# MACH_NGUYEN_LY.net
KiCad netlist of a schematic drawn in Altium Designer
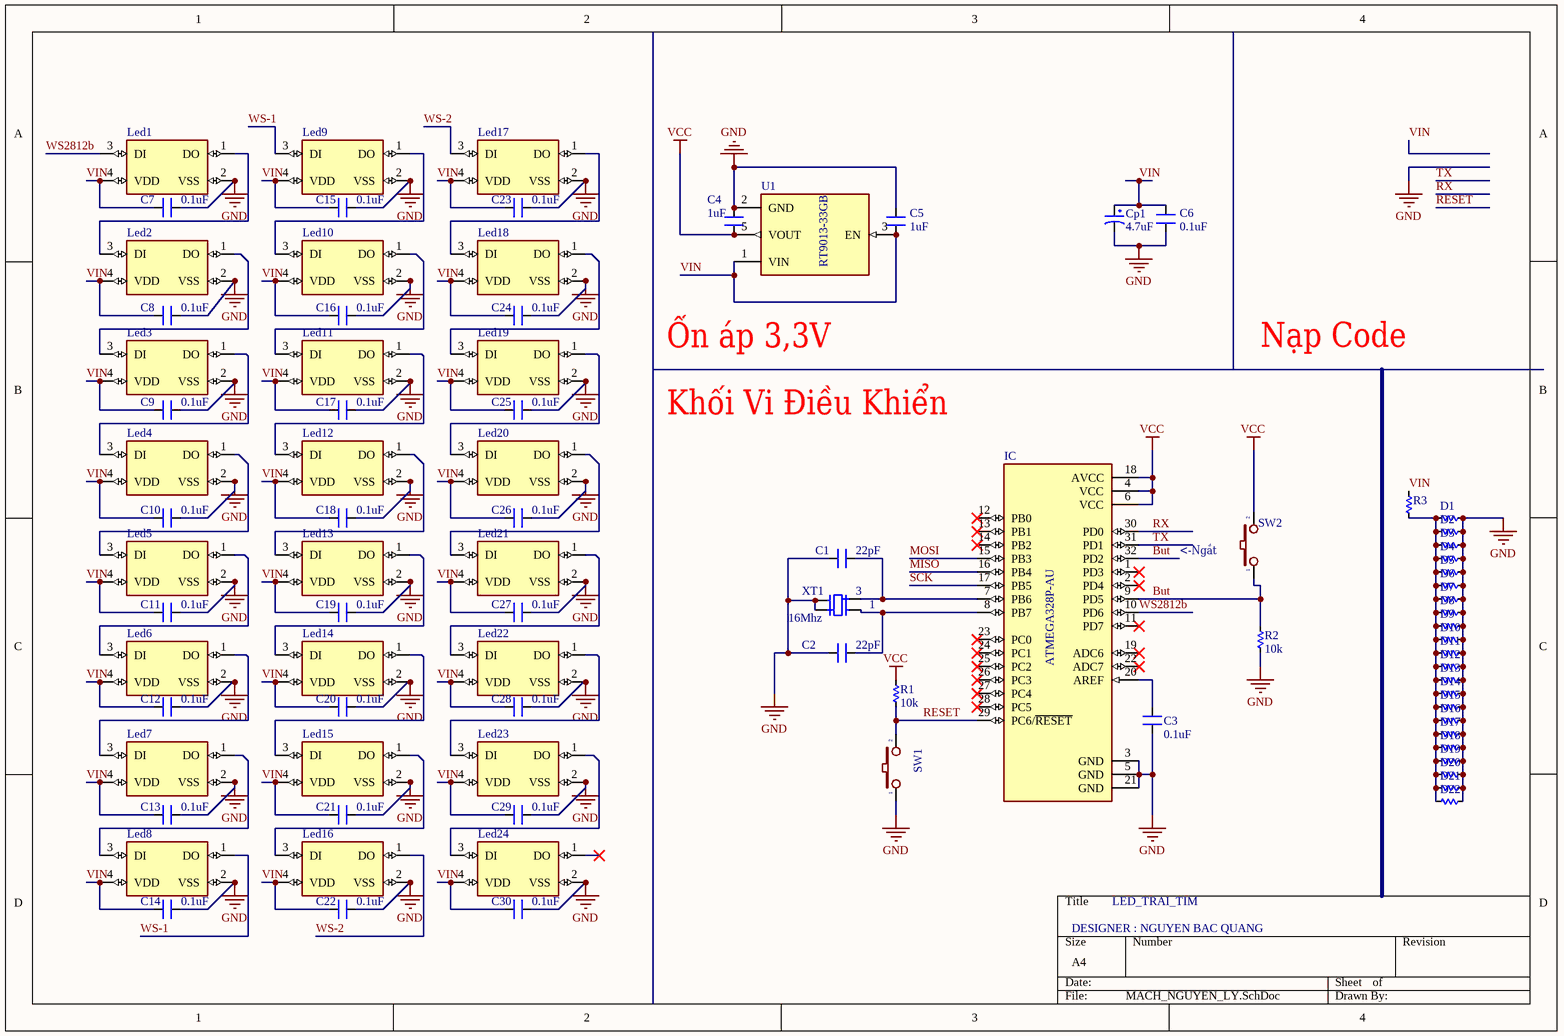
[diagram p0: MACH_NGUYEN_LY.SchDoc]

(export (version "E")
  (design (tool "Eeschema 10.0.6"))
  (components
    (comp (ref "C1") (value "22pF") (footprint "CN-SMD-0805") (libsource (lib "LIBRARY") (part "CN")))
    (comp (ref "C2") (value "22pF") (footprint "CN-SMD-0805") (libsource (lib "LIBRARY") (part "CN")))
    (comp (ref "C3") (value "0.1uF") (footprint "CN-SMD-0603") (libsource (lib "LIBRARY") (part "CN")))
    (comp (ref "C4") (value "1uF") (footprint "CN-SMD-0805") (libsource (lib "LIBRARY") (part "CN")))
    (comp (ref "C5") (value "1uF") (footprint "CN-SMD-0805") (libsource (lib "LIBRARY") (part "CN")))
    (comp (ref "C6") (value "0.1uF") (footprint "CN-SMD-0603") (libsource (lib "LIBRARY") (part "CN")))
    (comp (ref "C7") (value "0.1uF") (footprint "CN-SMD-0603") (libsource (lib "LIBRARY") (part "CN")))
    (comp (ref "C8") (value "0.1uF") (footprint "CN-SMD-0603") (libsource (lib "LIBRARY") (part "CN")))
    (comp (ref "C9") (value "0.1uF") (footprint "CN-SMD-0603") (libsource (lib "LIBRARY") (part "CN")))
    (comp (ref "C10") (value "0.1uF") (footprint "CN-SMD-0603") (libsource (lib "LIBRARY") (part "CN")))
    (comp (ref "C11") (value "0.1uF") (footprint "CN-SMD-0603") (libsource (lib "LIBRARY") (part "CN")))
    (comp (ref "C12") (value "0.1uF") (footprint "CN-SMD-0603") (libsource (lib "LIBRARY") (part "CN")))
    (comp (ref "C13") (value "0.1uF") (footprint "CN-SMD-0603") (libsource (lib "LIBRARY") (part "CN")))
    (comp (ref "C14") (value "0.1uF") (footprint "CN-SMD-0603") (libsource (lib "LIBRARY") (part "CN")))
    (comp (ref "C15") (value "0.1uF") (footprint "CN-SMD-0603") (libsource (lib "LIBRARY") (part "CN")))
    (comp (ref "C16") (value "0.1uF") (footprint "CN-SMD-0603") (libsource (lib "LIBRARY") (part "CN")))
    (comp (ref "C17") (value "0.1uF") (footprint "CN-SMD-0603") (libsource (lib "LIBRARY") (part "CN")))
    (comp (ref "C18") (value "0.1uF") (footprint "CN-SMD-0603") (libsource (lib "LIBRARY") (part "CN")))
    (comp (ref "C19") (value "0.1uF") (footprint "CN-SMD-0603") (libsource (lib "LIBRARY") (part "CN")))
    (comp (ref "C20") (value "0.1uF") (footprint "CN-SMD-0603") (libsource (lib "LIBRARY") (part "CN")))
    (comp (ref "C21") (value "0.1uF") (footprint "CN-SMD-0603") (libsource (lib "LIBRARY") (part "CN")))
    (comp (ref "C22") (value "0.1uF") (footprint "CN-SMD-0603") (libsource (lib "LIBRARY") (part "CN")))
    (comp (ref "C23") (value "0.1uF") (footprint "CN-SMD-0603") (libsource (lib "LIBRARY") (part "CN")))
    (comp (ref "C24") (value "0.1uF") (footprint "CN-SMD-0603") (libsource (lib "LIBRARY") (part "CN")))
    (comp (ref "C25") (value "0.1uF") (footprint "CN-SMD-0603") (libsource (lib "LIBRARY") (part "CN")))
    (comp (ref "C26") (value "0.1uF") (footprint "CN-SMD-0603") (libsource (lib "LIBRARY") (part "CN")))
    (comp (ref "C27") (value "0.1uF") (footprint "CN-SMD-0603") (libsource (lib "LIBRARY") (part "CN")))
    (comp (ref "C28") (value "0.1uF") (footprint "CN-SMD-0603") (libsource (lib "LIBRARY") (part "CN")))
    (comp (ref "C29") (value "0.1uF") (footprint "CN-SMD-0603") (libsource (lib "LIBRARY") (part "CN")))
    (comp (ref "C30") (value "0.1uF") (footprint "CN-SMD-0603") (libsource (lib "LIBRARY") (part "CN")))
    (comp (ref "Cp1")
      (value "4.7uF")
      (footprint "tu tantalum smd3216")
      (description "Dán")
      (libsource (lib "Altium_Lib_by_KhueNguyenCreator") (part "Tu tantalum 4.7uF 16V SMD3216"))
    )
    (comp (ref "D1")
      (value "~")
      (footprint "RES-SMD-0603")
      (description "Resistor")
      (fields
        (field (name "MANUFACTURER") "Generic Components")
        (field (name "PUBLISHER") "Altium Hobart Technology Centre")
      )
      (libsource (lib "LIBRARY") (part "Res-SMD"))
    )
    (comp (ref "D2")
      (value "~")
      (footprint "RES-SMD-0603")
      (description "Resistor")
      (fields
        (field (name "MANUFACTURER") "Generic Components")
        (field (name "PUBLISHER") "Altium Hobart Technology Centre")
      )
      (libsource (lib "LIBRARY") (part "Res-SMD"))
    )
    (comp (ref "D3")
      (value "~")
      (footprint "RES-SMD-0603")
      (description "Resistor")
      (fields
        (field (name "MANUFACTURER") "Generic Components")
        (field (name "PUBLISHER") "Altium Hobart Technology Centre")
      )
      (libsource (lib "LIBRARY") (part "Res-SMD"))
    )
    (comp (ref "D4")
      (value "~")
      (footprint "RES-SMD-0603")
      (description "Resistor")
      (fields
        (field (name "MANUFACTURER") "Generic Components")
        (field (name "PUBLISHER") "Altium Hobart Technology Centre")
      )
      (libsource (lib "LIBRARY") (part "Res-SMD"))
    )
    (comp (ref "D5")
      (value "~")
      (footprint "RES-SMD-0603")
      (description "Resistor")
      (fields
        (field (name "MANUFACTURER") "Generic Components")
        (field (name "PUBLISHER") "Altium Hobart Technology Centre")
      )
      (libsource (lib "LIBRARY") (part "Res-SMD"))
    )
    (comp (ref "D6")
      (value "~")
      (footprint "RES-SMD-0603")
      (description "Resistor")
      (fields
        (field (name "MANUFACTURER") "Generic Components")
        (field (name "PUBLISHER") "Altium Hobart Technology Centre")
      )
      (libsource (lib "LIBRARY") (part "Res-SMD"))
    )
    (comp (ref "D7")
      (value "~")
      (footprint "RES-SMD-0603")
      (description "Resistor")
      (fields
        (field (name "MANUFACTURER") "Generic Components")
        (field (name "PUBLISHER") "Altium Hobart Technology Centre")
      )
      (libsource (lib "LIBRARY") (part "Res-SMD"))
    )
    (comp (ref "D8")
      (value "~")
      (footprint "RES-SMD-0603")
      (description "Resistor")
      (fields
        (field (name "MANUFACTURER") "Generic Components")
        (field (name "PUBLISHER") "Altium Hobart Technology Centre")
      )
      (libsource (lib "LIBRARY") (part "Res-SMD"))
    )
    (comp (ref "D9")
      (value "~")
      (footprint "RES-SMD-0603")
      (description "Resistor")
      (fields
        (field (name "MANUFACTURER") "Generic Components")
        (field (name "PUBLISHER") "Altium Hobart Technology Centre")
      )
      (libsource (lib "LIBRARY") (part "Res-SMD"))
    )
    (comp (ref "D10")
      (value "~")
      (footprint "RES-SMD-0603")
      (description "Resistor")
      (fields
        (field (name "MANUFACTURER") "Generic Components")
        (field (name "PUBLISHER") "Altium Hobart Technology Centre")
      )
      (libsource (lib "LIBRARY") (part "Res-SMD"))
    )
    (comp (ref "D11")
      (value "~")
      (footprint "RES-SMD-0603")
      (description "Resistor")
      (fields
        (field (name "MANUFACTURER") "Generic Components")
        (field (name "PUBLISHER") "Altium Hobart Technology Centre")
      )
      (libsource (lib "LIBRARY") (part "Res-SMD"))
    )
    (comp (ref "D12")
      (value "~")
      (footprint "RES-SMD-0603")
      (description "Resistor")
      (fields
        (field (name "MANUFACTURER") "Generic Components")
        (field (name "PUBLISHER") "Altium Hobart Technology Centre")
      )
      (libsource (lib "LIBRARY") (part "Res-SMD"))
    )
    (comp (ref "D13")
      (value "~")
      (footprint "RES-SMD-0603")
      (description "Resistor")
      (fields
        (field (name "MANUFACTURER") "Generic Components")
        (field (name "PUBLISHER") "Altium Hobart Technology Centre")
      )
      (libsource (lib "LIBRARY") (part "Res-SMD"))
    )
    (comp (ref "D14")
      (value "~")
      (footprint "RES-SMD-0603")
      (description "Resistor")
      (fields
        (field (name "MANUFACTURER") "Generic Components")
        (field (name "PUBLISHER") "Altium Hobart Technology Centre")
      )
      (libsource (lib "LIBRARY") (part "Res-SMD"))
    )
    (comp (ref "D15")
      (value "~")
      (footprint "RES-SMD-0603")
      (description "Resistor")
      (fields
        (field (name "MANUFACTURER") "Generic Components")
        (field (name "PUBLISHER") "Altium Hobart Technology Centre")
      )
      (libsource (lib "LIBRARY") (part "Res-SMD"))
    )
    (comp (ref "D16")
      (value "~")
      (footprint "RES-SMD-0603")
      (description "Resistor")
      (fields
        (field (name "MANUFACTURER") "Generic Components")
        (field (name "PUBLISHER") "Altium Hobart Technology Centre")
      )
      (libsource (lib "LIBRARY") (part "Res-SMD"))
    )
    (comp (ref "D17")
      (value "~")
      (footprint "RES-SMD-0603")
      (description "Resistor")
      (fields
        (field (name "MANUFACTURER") "Generic Components")
        (field (name "PUBLISHER") "Altium Hobart Technology Centre")
      )
      (libsource (lib "LIBRARY") (part "Res-SMD"))
    )
    (comp (ref "D18")
      (value "~")
      (footprint "RES-SMD-0603")
      (description "Resistor")
      (fields
        (field (name "MANUFACTURER") "Generic Components")
        (field (name "PUBLISHER") "Altium Hobart Technology Centre")
      )
      (libsource (lib "LIBRARY") (part "Res-SMD"))
    )
    (comp (ref "D19")
      (value "~")
      (footprint "RES-SMD-0603")
      (description "Resistor")
      (fields
        (field (name "MANUFACTURER") "Generic Components")
        (field (name "PUBLISHER") "Altium Hobart Technology Centre")
      )
      (libsource (lib "LIBRARY") (part "Res-SMD"))
    )
    (comp (ref "D20")
      (value "~")
      (footprint "RES-SMD-0603")
      (description "Resistor")
      (fields
        (field (name "MANUFACTURER") "Generic Components")
        (field (name "PUBLISHER") "Altium Hobart Technology Centre")
      )
      (libsource (lib "LIBRARY") (part "Res-SMD"))
    )
    (comp (ref "D21")
      (value "~")
      (footprint "RES-SMD-0603")
      (description "Resistor")
      (fields
        (field (name "MANUFACTURER") "Generic Components")
        (field (name "PUBLISHER") "Altium Hobart Technology Centre")
      )
      (libsource (lib "LIBRARY") (part "Res-SMD"))
    )
    (comp (ref "D22")
      (value "~")
      (footprint "RES-SMD-0603")
      (description "Resistor")
      (fields
        (field (name "MANUFACTURER") "Generic Components")
        (field (name "PUBLISHER") "Altium Hobart Technology Centre")
      )
      (libsource (lib "LIBRARY") (part "Res-SMD"))
    )
    (comp (ref "IC")
      (value "ATMEGA328P-AU")
      (footprint "QFP80P900X900X120-32N")
      (description "AVR AVRÂ® ATmega Microcontroller IC 8-Bit 20MHz 32KB (16K x 16) FLASH 32-TQFP (7x7)")
      (fields (field (name "MF") "Microchip Technology"))
      (libsource (lib "ATMEGA328P-AU") (part "ATMEGA328P-AU"))
    )
    (comp (ref "Led1")
      (value "~")
      (footprint "WS2812B-2020")
      (description "Programmable LED; SMD; 2020; RGB; 2x2x0.84mm; 3.7Ã·5.3V; 2kHz")
      (fields (field (name "MF") "WorldSemi") (field (name "MP") "WS2812B-2020"))
      (libsource (lib "WS2812B-2020") (part "WS2812B-2020"))
    )
    (comp (ref "Led2")
      (value "~")
      (footprint "WS2812B-2020")
      (description "Programmable LED; SMD; 2020; RGB; 2x2x0.84mm; 3.7Ã·5.3V; 2kHz")
      (fields (field (name "MF") "WorldSemi") (field (name "MP") "WS2812B-2020"))
      (libsource (lib "WS2812B-2020") (part "WS2812B-2020"))
    )
    (comp (ref "Led3")
      (value "~")
      (footprint "WS2812B-2020")
      (description "Programmable LED; SMD; 2020; RGB; 2x2x0.84mm; 3.7Ã·5.3V; 2kHz")
      (fields (field (name "MF") "WorldSemi") (field (name "MP") "WS2812B-2020"))
      (libsource (lib "WS2812B-2020") (part "WS2812B-2020"))
    )
    (comp (ref "Led4")
      (value "~")
      (footprint "WS2812B-2020")
      (description "Programmable LED; SMD; 2020; RGB; 2x2x0.84mm; 3.7Ã·5.3V; 2kHz")
      (fields (field (name "MF") "WorldSemi") (field (name "MP") "WS2812B-2020"))
      (libsource (lib "WS2812B-2020") (part "WS2812B-2020"))
    )
    (comp (ref "Led5")
      (value "~")
      (footprint "WS2812B-2020")
      (description "Programmable LED; SMD; 2020; RGB; 2x2x0.84mm; 3.7Ã·5.3V; 2kHz")
      (fields (field (name "MF") "WorldSemi") (field (name "MP") "WS2812B-2020"))
      (libsource (lib "WS2812B-2020") (part "WS2812B-2020"))
    )
    (comp (ref "Led6")
      (value "~")
      (footprint "WS2812B-2020")
      (description "Programmable LED; SMD; 2020; RGB; 2x2x0.84mm; 3.7Ã·5.3V; 2kHz")
      (fields (field (name "MF") "WorldSemi") (field (name "MP") "WS2812B-2020"))
      (libsource (lib "WS2812B-2020") (part "WS2812B-2020"))
    )
    (comp (ref "Led7")
      (value "~")
      (footprint "WS2812B-2020")
      (description "Programmable LED; SMD; 2020; RGB; 2x2x0.84mm; 3.7Ã·5.3V; 2kHz")
      (fields (field (name "MF") "WorldSemi") (field (name "MP") "WS2812B-2020"))
      (libsource (lib "WS2812B-2020") (part "WS2812B-2020"))
    )
    (comp (ref "Led8")
      (value "~")
      (footprint "WS2812B-2020")
      (description "Programmable LED; SMD; 2020; RGB; 2x2x0.84mm; 3.7Ã·5.3V; 2kHz")
      (fields (field (name "MF") "WorldSemi") (field (name "MP") "WS2812B-2020"))
      (libsource (lib "WS2812B-2020") (part "WS2812B-2020"))
    )
    (comp (ref "Led9")
      (value "~")
      (footprint "WS2812B-2020")
      (description "Programmable LED; SMD; 2020; RGB; 2x2x0.84mm; 3.7Ã·5.3V; 2kHz")
      (fields (field (name "MF") "WorldSemi") (field (name "MP") "WS2812B-2020"))
      (libsource (lib "WS2812B-2020") (part "WS2812B-2020"))
    )
    (comp (ref "Led10")
      (value "~")
      (footprint "WS2812B-2020")
      (description "Programmable LED; SMD; 2020; RGB; 2x2x0.84mm; 3.7Ã·5.3V; 2kHz")
      (fields (field (name "MF") "WorldSemi") (field (name "MP") "WS2812B-2020"))
      (libsource (lib "WS2812B-2020") (part "WS2812B-2020"))
    )
    (comp (ref "Led11")
      (value "~")
      (footprint "WS2812B-2020")
      (description "Programmable LED; SMD; 2020; RGB; 2x2x0.84mm; 3.7Ã·5.3V; 2kHz")
      (fields (field (name "MF") "WorldSemi") (field (name "MP") "WS2812B-2020"))
      (libsource (lib "WS2812B-2020") (part "WS2812B-2020"))
    )
    (comp (ref "Led12")
      (value "~")
      (footprint "WS2812B-2020")
      (description "Programmable LED; SMD; 2020; RGB; 2x2x0.84mm; 3.7Ã·5.3V; 2kHz")
      (fields (field (name "MF") "WorldSemi") (field (name "MP") "WS2812B-2020"))
      (libsource (lib "WS2812B-2020") (part "WS2812B-2020"))
    )
    (comp (ref "Led13")
      (value "~")
      (footprint "WS2812B-2020")
      (description "Programmable LED; SMD; 2020; RGB; 2x2x0.84mm; 3.7Ã·5.3V; 2kHz")
      (fields (field (name "MF") "WorldSemi") (field (name "MP") "WS2812B-2020"))
      (libsource (lib "WS2812B-2020") (part "WS2812B-2020"))
    )
    (comp (ref "Led14")
      (value "~")
      (footprint "WS2812B-2020")
      (description "Programmable LED; SMD; 2020; RGB; 2x2x0.84mm; 3.7Ã·5.3V; 2kHz")
      (fields (field (name "MF") "WorldSemi") (field (name "MP") "WS2812B-2020"))
      (libsource (lib "WS2812B-2020") (part "WS2812B-2020"))
    )
    (comp (ref "Led15")
      (value "~")
      (footprint "WS2812B-2020")
      (description "Programmable LED; SMD; 2020; RGB; 2x2x0.84mm; 3.7Ã·5.3V; 2kHz")
      (fields (field (name "MF") "WorldSemi") (field (name "MP") "WS2812B-2020"))
      (libsource (lib "WS2812B-2020") (part "WS2812B-2020"))
    )
    (comp (ref "Led16")
      (value "~")
      (footprint "WS2812B-2020")
      (description "Programmable LED; SMD; 2020; RGB; 2x2x0.84mm; 3.7Ã·5.3V; 2kHz")
      (fields (field (name "MF") "WorldSemi") (field (name "MP") "WS2812B-2020"))
      (libsource (lib "WS2812B-2020") (part "WS2812B-2020"))
    )
    (comp (ref "Led17")
      (value "~")
      (footprint "WS2812B-2020")
      (description "Programmable LED; SMD; 2020; RGB; 2x2x0.84mm; 3.7Ã·5.3V; 2kHz")
      (fields (field (name "MF") "WorldSemi") (field (name "MP") "WS2812B-2020"))
      (libsource (lib "WS2812B-2020") (part "WS2812B-2020"))
    )
    (comp (ref "Led18")
      (value "~")
      (footprint "WS2812B-2020")
      (description "Programmable LED; SMD; 2020; RGB; 2x2x0.84mm; 3.7Ã·5.3V; 2kHz")
      (fields (field (name "MF") "WorldSemi") (field (name "MP") "WS2812B-2020"))
      (libsource (lib "WS2812B-2020") (part "WS2812B-2020"))
    )
    (comp (ref "Led19")
      (value "~")
      (footprint "WS2812B-2020")
      (description "Programmable LED; SMD; 2020; RGB; 2x2x0.84mm; 3.7Ã·5.3V; 2kHz")
      (fields (field (name "MF") "WorldSemi") (field (name "MP") "WS2812B-2020"))
      (libsource (lib "WS2812B-2020") (part "WS2812B-2020"))
    )
    (comp (ref "Led20")
      (value "~")
      (footprint "WS2812B-2020")
      (description "Programmable LED; SMD; 2020; RGB; 2x2x0.84mm; 3.7Ã·5.3V; 2kHz")
      (fields (field (name "MF") "WorldSemi") (field (name "MP") "WS2812B-2020"))
      (libsource (lib "WS2812B-2020") (part "WS2812B-2020"))
    )
    (comp (ref "Led21")
      (value "~")
      (footprint "WS2812B-2020")
      (description "Programmable LED; SMD; 2020; RGB; 2x2x0.84mm; 3.7Ã·5.3V; 2kHz")
      (fields (field (name "MF") "WorldSemi") (field (name "MP") "WS2812B-2020"))
      (libsource (lib "WS2812B-2020") (part "WS2812B-2020"))
    )
    (comp (ref "Led22")
      (value "~")
      (footprint "WS2812B-2020")
      (description "Programmable LED; SMD; 2020; RGB; 2x2x0.84mm; 3.7Ã·5.3V; 2kHz")
      (fields (field (name "MF") "WorldSemi") (field (name "MP") "WS2812B-2020"))
      (libsource (lib "WS2812B-2020") (part "WS2812B-2020"))
    )
    (comp (ref "Led23")
      (value "~")
      (footprint "WS2812B-2020")
      (description "Programmable LED; SMD; 2020; RGB; 2x2x0.84mm; 3.7Ã·5.3V; 2kHz")
      (fields (field (name "MF") "WorldSemi") (field (name "MP") "WS2812B-2020"))
      (libsource (lib "WS2812B-2020") (part "WS2812B-2020"))
    )
    (comp (ref "Led24")
      (value "~")
      (footprint "WS2812B-2020")
      (description "Programmable LED; SMD; 2020; RGB; 2x2x0.84mm; 3.7Ã·5.3V; 2kHz")
      (fields (field (name "MF") "WorldSemi") (field (name "MP") "WS2812B-2020"))
      (libsource (lib "WS2812B-2020") (part "WS2812B-2020"))
    )
    (comp (ref "R1")
      (value "10k")
      (footprint "RES-SMD-0603")
      (description "Resistor")
      (fields
        (field (name "MANUFACTURER") "Generic Components")
        (field (name "PUBLISHER") "Altium Hobart Technology Centre")
      )
      (libsource (lib "LIBRARY") (part "Res-SMD"))
    )
    (comp (ref "R2")
      (value "10k")
      (footprint "RES-SMD-0603")
      (description "Resistor")
      (fields
        (field (name "MANUFACTURER") "Generic Components")
        (field (name "PUBLISHER") "Altium Hobart Technology Centre")
      )
      (libsource (lib "LIBRARY") (part "Res-SMD"))
    )
    (comp (ref "R3")
      (value "~")
      (footprint "RES-SMD-0603")
      (description "Resistor")
      (fields
        (field (name "MANUFACTURER") "Generic Components")
        (field (name "PUBLISHER") "Altium Hobart Technology Centre")
      )
      (libsource (lib "LIBRARY") (part "Res-SMD"))
    )
    (comp (ref "SW1")
      (value "~")
      (footprint "SW1-SMD")
      (description "Switch button 2 pin")
      (libsource (lib "LIBRARY") (part "SW2"))
    )
    (comp (ref "SW2")
      (value "~")
      (footprint "SW1-SMD")
      (description "Switch button 2 pin")
      (libsource (lib "LIBRARY") (part "SW2"))
    )
    (comp (ref "U1")
      (value "RT9013-33GB")
      (footprint "SOT94P279X129-5N")
      (description "Linear Voltage Regulator IC 1 Output 500mA SOT-23-5")
      (fields (field (name "MF") "Richtek USA"))
      (libsource (lib "RT9013-33GB") (part "RT9013-33GB"))
    )
    (comp (ref "XT1")
      (value "16Mhz")
      (footprint "Thach Anh 4 chan 1")
      (description "Crystal For all Crystal 2pin.")
      (libsource (lib "Altium_Lib_by_KhueNguyenCreator") (part "Thach Anh 4 Chan SMD"))
    )
  )
  (nets
    (net (code "1") (name "/But") (class "Default")
      (node (ref "IC") (pin "32") (pinfunction "PD2_32") (pintype "bidirectional"))
      (node (ref "IC") (pin "9") (pinfunction "PD5_9") (pintype "bidirectional"))
      (node (ref "R2") (pin "1") (pinfunction "1_1") (pintype "passive"))
      (node (ref "SW2") (pin "1") (pinfunction "1_1") (pintype "passive"))
    )
    (net (code "2") (name "/MISO") (class "Default")
      (node (ref "IC") (pin "16") (pinfunction "PB4_16") (pintype "bidirectional"))
    )
    (net (code "3") (name "/MOSI") (class "Default")
      (node (ref "IC") (pin "15") (pinfunction "PB3_15") (pintype "bidirectional"))
    )
    (net (code "4") (name "/RESET") (class "Default")
      (node (ref "IC") (pin "29") (pinfunction "PC6/~{RESET}_29") (pintype "bidirectional"))
      (node (ref "R1") (pin "2") (pinfunction "2_2") (pintype "passive"))
      (node (ref "SW1") (pin "2") (pinfunction "2_2") (pintype "passive"))
    )
    (net (code "5") (name "/RX") (class "Default")
      (node (ref "IC") (pin "30") (pinfunction "PD0_30") (pintype "bidirectional"))
    )
    (net (code "6") (name "/SCK") (class "Default")
      (node (ref "IC") (pin "17") (pinfunction "PB5_17") (pintype "bidirectional"))
    )
    (net (code "7") (name "/TX") (class "Default")
      (node (ref "IC") (pin "31") (pinfunction "PD1_31") (pintype "bidirectional"))
    )
    (net (code "8") (name "/VIN") (class "Default")
      (node (ref "C10") (pin "1") (pinfunction "1_1") (pintype "passive"))
      (node (ref "C11") (pin "1") (pinfunction "1_1") (pintype "passive"))
      (node (ref "C12") (pin "1") (pinfunction "1_1") (pintype "passive"))
      (node (ref "C13") (pin "1") (pinfunction "1_1") (pintype "passive"))
      (node (ref "C14") (pin "1") (pinfunction "1_1") (pintype "passive"))
      (node (ref "C15") (pin "1") (pinfunction "1_1") (pintype "passive"))
      (node (ref "C16") (pin "1") (pinfunction "1_1") (pintype "passive"))
      (node (ref "C17") (pin "1") (pinfunction "1_1") (pintype "passive"))
      (node (ref "C18") (pin "1") (pinfunction "1_1") (pintype "passive"))
      (node (ref "C19") (pin "1") (pinfunction "1_1") (pintype "passive"))
      (node (ref "C20") (pin "1") (pinfunction "1_1") (pintype "passive"))
      (node (ref "C21") (pin "1") (pinfunction "1_1") (pintype "passive"))
      (node (ref "C22") (pin "1") (pinfunction "1_1") (pintype "passive"))
      (node (ref "C23") (pin "1") (pinfunction "1_1") (pintype "passive"))
      (node (ref "C24") (pin "1") (pinfunction "1_1") (pintype "passive"))
      (node (ref "C25") (pin "1") (pinfunction "1_1") (pintype "passive"))
      (node (ref "C26") (pin "1") (pinfunction "1_1") (pintype "passive"))
      (node (ref "C27") (pin "1") (pinfunction "1_1") (pintype "passive"))
      (node (ref "C28") (pin "1") (pinfunction "1_1") (pintype "passive"))
      (node (ref "C29") (pin "1") (pinfunction "1_1") (pintype "passive"))
      (node (ref "C30") (pin "1") (pinfunction "1_1") (pintype "passive"))
      (node (ref "C5") (pin "1") (pinfunction "1_1") (pintype "passive"))
      (node (ref "C6") (pin "1") (pinfunction "1_1") (pintype "passive"))
      (node (ref "C7") (pin "1") (pinfunction "1_1") (pintype "passive"))
      (node (ref "C8") (pin "1") (pinfunction "1_1") (pintype "passive"))
      (node (ref "C9") (pin "1") (pinfunction "1_1") (pintype "passive"))
      (node (ref "Cp1") (pin "1") (pinfunction "1_1") (pintype "passive"))
      (node (ref "Led1") (pin "4") (pinfunction "VDD_4") (pintype "bidirectional"))
      (node (ref "Led10") (pin "4") (pinfunction "VDD_4") (pintype "bidirectional"))
      (node (ref "Led11") (pin "4") (pinfunction "VDD_4") (pintype "bidirectional"))
      (node (ref "Led12") (pin "4") (pinfunction "VDD_4") (pintype "bidirectional"))
      (node (ref "Led13") (pin "4") (pinfunction "VDD_4") (pintype "bidirectional"))
      (node (ref "Led14") (pin "4") (pinfunction "VDD_4") (pintype "bidirectional"))
      (node (ref "Led15") (pin "4") (pinfunction "VDD_4") (pintype "bidirectional"))
      (node (ref "Led16") (pin "4") (pinfunction "VDD_4") (pintype "bidirectional"))
      (node (ref "Led17") (pin "4") (pinfunction "VDD_4") (pintype "bidirectional"))
      (node (ref "Led18") (pin "4") (pinfunction "VDD_4") (pintype "bidirectional"))
      (node (ref "Led19") (pin "4") (pinfunction "VDD_4") (pintype "bidirectional"))
      (node (ref "Led2") (pin "4") (pinfunction "VDD_4") (pintype "bidirectional"))
      (node (ref "Led20") (pin "4") (pinfunction "VDD_4") (pintype "bidirectional"))
      (node (ref "Led21") (pin "4") (pinfunction "VDD_4") (pintype "bidirectional"))
      (node (ref "Led22") (pin "4") (pinfunction "VDD_4") (pintype "bidirectional"))
      (node (ref "Led23") (pin "4") (pinfunction "VDD_4") (pintype "bidirectional"))
      (node (ref "Led24") (pin "4") (pinfunction "VDD_4") (pintype "bidirectional"))
      (node (ref "Led3") (pin "4") (pinfunction "VDD_4") (pintype "bidirectional"))
      (node (ref "Led4") (pin "4") (pinfunction "VDD_4") (pintype "bidirectional"))
      (node (ref "Led5") (pin "4") (pinfunction "VDD_4") (pintype "bidirectional"))
      (node (ref "Led6") (pin "4") (pinfunction "VDD_4") (pintype "bidirectional"))
      (node (ref "Led7") (pin "4") (pinfunction "VDD_4") (pintype "bidirectional"))
      (node (ref "Led8") (pin "4") (pinfunction "VDD_4") (pintype "bidirectional"))
      (node (ref "Led9") (pin "4") (pinfunction "VDD_4") (pintype "bidirectional"))
      (node (ref "R3") (pin "1") (pinfunction "1_1") (pintype "passive"))
      (node (ref "U1") (pin "1") (pinfunction "VIN_1") (pintype "power_in"))
      (node (ref "U1") (pin "3") (pinfunction "EN_3") (pintype "input"))
    )
    (net (code "9") (name "/WS-1") (class "Default")
      (node (ref "Led8") (pin "1") (pinfunction "DO_1") (pintype "bidirectional"))
      (node (ref "Led9") (pin "3") (pinfunction "DI_3") (pintype "bidirectional"))
    )
    (net (code "10") (name "/WS-2") (class "Default")
      (node (ref "Led16") (pin "1") (pinfunction "DO_1") (pintype "bidirectional"))
      (node (ref "Led17") (pin "3") (pinfunction "DI_3") (pintype "bidirectional"))
    )
    (net (code "11") (name "/WS2812b") (class "Default")
      (node (ref "IC") (pin "10") (pinfunction "PD6_10") (pintype "bidirectional"))
      (node (ref "Led1") (pin "3") (pinfunction "DI_3") (pintype "bidirectional"))
    )
    (net (code "12") (name "GND") (class "Default")
      (node (ref "C1") (pin "1") (pinfunction "1_1") (pintype "passive"))
      (node (ref "C10") (pin "2") (pinfunction "2_2") (pintype "passive"))
      (node (ref "C11") (pin "2") (pinfunction "2_2") (pintype "passive"))
      (node (ref "C12") (pin "2") (pinfunction "2_2") (pintype "passive"))
      (node (ref "C13") (pin "2") (pinfunction "2_2") (pintype "passive"))
      (node (ref "C14") (pin "2") (pinfunction "2_2") (pintype "passive"))
      (node (ref "C15") (pin "2") (pinfunction "2_2") (pintype "passive"))
      (node (ref "C16") (pin "2") (pinfunction "2_2") (pintype "passive"))
      (node (ref "C17") (pin "2") (pinfunction "2_2") (pintype "passive"))
      (node (ref "C18") (pin "2") (pinfunction "2_2") (pintype "passive"))
      (node (ref "C19") (pin "2") (pinfunction "2_2") (pintype "passive"))
      (node (ref "C2") (pin "1") (pinfunction "1_1") (pintype "passive"))
      (node (ref "C20") (pin "2") (pinfunction "2_2") (pintype "passive"))
      (node (ref "C21") (pin "2") (pinfunction "2_2") (pintype "passive"))
      (node (ref "C22") (pin "2") (pinfunction "2_2") (pintype "passive"))
      (node (ref "C23") (pin "2") (pinfunction "2_2") (pintype "passive"))
      (node (ref "C24") (pin "2") (pinfunction "2_2") (pintype "passive"))
      (node (ref "C25") (pin "2") (pinfunction "2_2") (pintype "passive"))
      (node (ref "C26") (pin "2") (pinfunction "2_2") (pintype "passive"))
      (node (ref "C27") (pin "2") (pinfunction "2_2") (pintype "passive"))
      (node (ref "C28") (pin "2") (pinfunction "2_2") (pintype "passive"))
      (node (ref "C29") (pin "2") (pinfunction "2_2") (pintype "passive"))
      (node (ref "C3") (pin "2") (pinfunction "2_2") (pintype "passive"))
      (node (ref "C30") (pin "2") (pinfunction "2_2") (pintype "passive"))
      (node (ref "C4") (pin "1") (pinfunction "1_1") (pintype "passive"))
      (node (ref "C5") (pin "2") (pinfunction "2_2") (pintype "passive"))
      (node (ref "C6") (pin "2") (pinfunction "2_2") (pintype "passive"))
      (node (ref "C7") (pin "2") (pinfunction "2_2") (pintype "passive"))
      (node (ref "C8") (pin "2") (pinfunction "2_2") (pintype "passive"))
      (node (ref "C9") (pin "2") (pinfunction "2_2") (pintype "passive"))
      (node (ref "Cp1") (pin "2") (pinfunction "2_2") (pintype "passive"))
      (node (ref "D1") (pin "1") (pinfunction "1_1") (pintype "passive"))
      (node (ref "D10") (pin "1") (pinfunction "1_1") (pintype "passive"))
      (node (ref "D11") (pin "1") (pinfunction "1_1") (pintype "passive"))
      (node (ref "D12") (pin "1") (pinfunction "1_1") (pintype "passive"))
      (node (ref "D13") (pin "1") (pinfunction "1_1") (pintype "passive"))
      (node (ref "D14") (pin "1") (pinfunction "1_1") (pintype "passive"))
      (node (ref "D15") (pin "1") (pinfunction "1_1") (pintype "passive"))
      (node (ref "D16") (pin "1") (pinfunction "1_1") (pintype "passive"))
      (node (ref "D17") (pin "1") (pinfunction "1_1") (pintype "passive"))
      (node (ref "D18") (pin "1") (pinfunction "1_1") (pintype "passive"))
      (node (ref "D19") (pin "1") (pinfunction "1_1") (pintype "passive"))
      (node (ref "D2") (pin "1") (pinfunction "1_1") (pintype "passive"))
      (node (ref "D20") (pin "1") (pinfunction "1_1") (pintype "passive"))
      (node (ref "D21") (pin "1") (pinfunction "1_1") (pintype "passive"))
      (node (ref "D22") (pin "1") (pinfunction "1_1") (pintype "passive"))
      (node (ref "D3") (pin "1") (pinfunction "1_1") (pintype "passive"))
      (node (ref "D4") (pin "1") (pinfunction "1_1") (pintype "passive"))
      (node (ref "D5") (pin "1") (pinfunction "1_1") (pintype "passive"))
      (node (ref "D6") (pin "1") (pinfunction "1_1") (pintype "passive"))
      (node (ref "D7") (pin "1") (pinfunction "1_1") (pintype "passive"))
      (node (ref "D8") (pin "1") (pinfunction "1_1") (pintype "passive"))
      (node (ref "D9") (pin "1") (pinfunction "1_1") (pintype "passive"))
      (node (ref "IC") (pin "21") (pinfunction "GND_21") (pintype "power_in"))
      (node (ref "IC") (pin "3") (pinfunction "GND_3") (pintype "power_in"))
      (node (ref "IC") (pin "5") (pinfunction "GND_5") (pintype "power_in"))
      (node (ref "Led1") (pin "2") (pinfunction "VSS_2") (pintype "bidirectional"))
      (node (ref "Led10") (pin "2") (pinfunction "VSS_2") (pintype "bidirectional"))
      (node (ref "Led11") (pin "2") (pinfunction "VSS_2") (pintype "bidirectional"))
      (node (ref "Led12") (pin "2") (pinfunction "VSS_2") (pintype "bidirectional"))
      (node (ref "Led13") (pin "2") (pinfunction "VSS_2") (pintype "bidirectional"))
      (node (ref "Led14") (pin "2") (pinfunction "VSS_2") (pintype "bidirectional"))
      (node (ref "Led15") (pin "2") (pinfunction "VSS_2") (pintype "bidirectional"))
      (node (ref "Led16") (pin "2") (pinfunction "VSS_2") (pintype "bidirectional"))
      (node (ref "Led17") (pin "2") (pinfunction "VSS_2") (pintype "bidirectional"))
      (node (ref "Led18") (pin "2") (pinfunction "VSS_2") (pintype "bidirectional"))
      (node (ref "Led19") (pin "2") (pinfunction "VSS_2") (pintype "bidirectional"))
      (node (ref "Led2") (pin "2") (pinfunction "VSS_2") (pintype "bidirectional"))
      (node (ref "Led20") (pin "2") (pinfunction "VSS_2") (pintype "bidirectional"))
      (node (ref "Led21") (pin "2") (pinfunction "VSS_2") (pintype "bidirectional"))
      (node (ref "Led22") (pin "2") (pinfunction "VSS_2") (pintype "bidirectional"))
      (node (ref "Led23") (pin "2") (pinfunction "VSS_2") (pintype "bidirectional"))
      (node (ref "Led24") (pin "2") (pinfunction "VSS_2") (pintype "bidirectional"))
      (node (ref "Led3") (pin "2") (pinfunction "VSS_2") (pintype "bidirectional"))
      (node (ref "Led4") (pin "2") (pinfunction "VSS_2") (pintype "bidirectional"))
      (node (ref "Led5") (pin "2") (pinfunction "VSS_2") (pintype "bidirectional"))
      (node (ref "Led6") (pin "2") (pinfunction "VSS_2") (pintype "bidirectional"))
      (node (ref "Led7") (pin "2") (pinfunction "VSS_2") (pintype "bidirectional"))
      (node (ref "Led8") (pin "2") (pinfunction "VSS_2") (pintype "bidirectional"))
      (node (ref "Led9") (pin "2") (pinfunction "VSS_2") (pintype "bidirectional"))
      (node (ref "R2") (pin "2") (pinfunction "2_2") (pintype "passive"))
      (node (ref "SW1") (pin "1") (pinfunction "1_1") (pintype "passive"))
      (node (ref "U1") (pin "2") (pinfunction "GND_2") (pintype "power_in"))
      (node (ref "XT1") (pin "2") (pinfunction "2_2") (pintype "passive"))
      (node (ref "XT1") (pin "4") (pinfunction "4_4") (pintype "passive"))
    )
    (net (code "13") (name "Net-(D1-Pad2)") (class "Default")
      (node (ref "D1") (pin "2") (pinfunction "2_2") (pintype "passive"))
      (node (ref "D10") (pin "2") (pinfunction "2_2") (pintype "passive"))
      (node (ref "D11") (pin "2") (pinfunction "2_2") (pintype "passive"))
      (node (ref "D12") (pin "2") (pinfunction "2_2") (pintype "passive"))
      (node (ref "D13") (pin "2") (pinfunction "2_2") (pintype "passive"))
      (node (ref "D14") (pin "2") (pinfunction "2_2") (pintype "passive"))
      (node (ref "D15") (pin "2") (pinfunction "2_2") (pintype "passive"))
      (node (ref "D16") (pin "2") (pinfunction "2_2") (pintype "passive"))
      (node (ref "D17") (pin "2") (pinfunction "2_2") (pintype "passive"))
      (node (ref "D18") (pin "2") (pinfunction "2_2") (pintype "passive"))
      (node (ref "D19") (pin "2") (pinfunction "2_2") (pintype "passive"))
      (node (ref "D2") (pin "2") (pinfunction "2_2") (pintype "passive"))
      (node (ref "D20") (pin "2") (pinfunction "2_2") (pintype "passive"))
      (node (ref "D21") (pin "2") (pinfunction "2_2") (pintype "passive"))
      (node (ref "D22") (pin "2") (pinfunction "2_2") (pintype "passive"))
      (node (ref "D3") (pin "2") (pinfunction "2_2") (pintype "passive"))
      (node (ref "D4") (pin "2") (pinfunction "2_2") (pintype "passive"))
      (node (ref "D5") (pin "2") (pinfunction "2_2") (pintype "passive"))
      (node (ref "D6") (pin "2") (pinfunction "2_2") (pintype "passive"))
      (node (ref "D7") (pin "2") (pinfunction "2_2") (pintype "passive"))
      (node (ref "D8") (pin "2") (pinfunction "2_2") (pintype "passive"))
      (node (ref "D9") (pin "2") (pinfunction "2_2") (pintype "passive"))
      (node (ref "R3") (pin "2") (pinfunction "2_2") (pintype "passive"))
    )
    (net (code "14") (name "Net-(IC-AREF)") (class "Default")
      (node (ref "C3") (pin "1") (pinfunction "1_1") (pintype "passive"))
      (node (ref "IC") (pin "20") (pinfunction "AREF_20") (pintype "input"))
    )
    (net (code "15") (name "Net-(IC-PB6)") (class "Default")
      (node (ref "C1") (pin "2") (pinfunction "2_2") (pintype "passive"))
      (node (ref "IC") (pin "7") (pinfunction "PB6_7") (pintype "bidirectional"))
      (node (ref "XT1") (pin "3") (pinfunction "3_3") (pintype "passive"))
    )
    (net (code "16") (name "Net-(IC-PB7)") (class "Default")
      (node (ref "C2") (pin "2") (pinfunction "2_2") (pintype "passive"))
      (node (ref "IC") (pin "8") (pinfunction "PB7_8") (pintype "bidirectional"))
      (node (ref "XT1") (pin "1") (pinfunction "1_1") (pintype "passive"))
    )
    (net (code "17") (name "Net-(Led1-DO)") (class "Default")
      (node (ref "Led1") (pin "1") (pinfunction "DO_1") (pintype "bidirectional"))
      (node (ref "Led2") (pin "3") (pinfunction "DI_3") (pintype "bidirectional"))
    )
    (net (code "18") (name "Net-(Led2-DO)") (class "Default")
      (node (ref "Led2") (pin "1") (pinfunction "DO_1") (pintype "bidirectional"))
      (node (ref "Led3") (pin "3") (pinfunction "DI_3") (pintype "bidirectional"))
    )
    (net (code "19") (name "Net-(Led3-DO)") (class "Default")
      (node (ref "Led3") (pin "1") (pinfunction "DO_1") (pintype "bidirectional"))
      (node (ref "Led4") (pin "3") (pinfunction "DI_3") (pintype "bidirectional"))
    )
    (net (code "20") (name "Net-(Led4-DO)") (class "Default")
      (node (ref "Led4") (pin "1") (pinfunction "DO_1") (pintype "bidirectional"))
      (node (ref "Led5") (pin "3") (pinfunction "DI_3") (pintype "bidirectional"))
    )
    (net (code "21") (name "Net-(Led5-DO)") (class "Default")
      (node (ref "Led5") (pin "1") (pinfunction "DO_1") (pintype "bidirectional"))
      (node (ref "Led6") (pin "3") (pinfunction "DI_3") (pintype "bidirectional"))
    )
    (net (code "22") (name "Net-(Led6-DO)") (class "Default")
      (node (ref "Led6") (pin "1") (pinfunction "DO_1") (pintype "bidirectional"))
      (node (ref "Led7") (pin "3") (pinfunction "DI_3") (pintype "bidirectional"))
    )
    (net (code "23") (name "Net-(Led7-DO)") (class "Default")
      (node (ref "Led7") (pin "1") (pinfunction "DO_1") (pintype "bidirectional"))
      (node (ref "Led8") (pin "3") (pinfunction "DI_3") (pintype "bidirectional"))
    )
    (net (code "24") (name "Net-(Led10-DI)") (class "Default")
      (node (ref "Led10") (pin "3") (pinfunction "DI_3") (pintype "bidirectional"))
      (node (ref "Led9") (pin "1") (pinfunction "DO_1") (pintype "bidirectional"))
    )
    (net (code "25") (name "Net-(Led10-DO)") (class "Default")
      (node (ref "Led10") (pin "1") (pinfunction "DO_1") (pintype "bidirectional"))
      (node (ref "Led11") (pin "3") (pinfunction "DI_3") (pintype "bidirectional"))
    )
    (net (code "26") (name "Net-(Led11-DO)") (class "Default")
      (node (ref "Led11") (pin "1") (pinfunction "DO_1") (pintype "bidirectional"))
      (node (ref "Led12") (pin "3") (pinfunction "DI_3") (pintype "bidirectional"))
    )
    (net (code "27") (name "Net-(Led12-DO)") (class "Default")
      (node (ref "Led12") (pin "1") (pinfunction "DO_1") (pintype "bidirectional"))
      (node (ref "Led13") (pin "3") (pinfunction "DI_3") (pintype "bidirectional"))
    )
    (net (code "28") (name "Net-(Led13-DO)") (class "Default")
      (node (ref "Led13") (pin "1") (pinfunction "DO_1") (pintype "bidirectional"))
      (node (ref "Led14") (pin "3") (pinfunction "DI_3") (pintype "bidirectional"))
    )
    (net (code "29") (name "Net-(Led14-DO)") (class "Default")
      (node (ref "Led14") (pin "1") (pinfunction "DO_1") (pintype "bidirectional"))
      (node (ref "Led15") (pin "3") (pinfunction "DI_3") (pintype "bidirectional"))
    )
    (net (code "30") (name "Net-(Led15-DO)") (class "Default")
      (node (ref "Led15") (pin "1") (pinfunction "DO_1") (pintype "bidirectional"))
      (node (ref "Led16") (pin "3") (pinfunction "DI_3") (pintype "bidirectional"))
    )
    (net (code "31") (name "Net-(Led17-DO)") (class "Default")
      (node (ref "Led17") (pin "1") (pinfunction "DO_1") (pintype "bidirectional"))
      (node (ref "Led18") (pin "3") (pinfunction "DI_3") (pintype "bidirectional"))
    )
    (net (code "32") (name "Net-(Led18-DO)") (class "Default")
      (node (ref "Led18") (pin "1") (pinfunction "DO_1") (pintype "bidirectional"))
      (node (ref "Led19") (pin "3") (pinfunction "DI_3") (pintype "bidirectional"))
    )
    (net (code "33") (name "Net-(Led19-DO)") (class "Default")
      (node (ref "Led19") (pin "1") (pinfunction "DO_1") (pintype "bidirectional"))
      (node (ref "Led20") (pin "3") (pinfunction "DI_3") (pintype "bidirectional"))
    )
    (net (code "34") (name "Net-(Led20-DO)") (class "Default")
      (node (ref "Led20") (pin "1") (pinfunction "DO_1") (pintype "bidirectional"))
      (node (ref "Led21") (pin "3") (pinfunction "DI_3") (pintype "bidirectional"))
    )
    (net (code "35") (name "Net-(Led21-DO)") (class "Default")
      (node (ref "Led21") (pin "1") (pinfunction "DO_1") (pintype "bidirectional"))
      (node (ref "Led22") (pin "3") (pinfunction "DI_3") (pintype "bidirectional"))
    )
    (net (code "36") (name "Net-(Led22-DO)") (class "Default")
      (node (ref "Led22") (pin "1") (pinfunction "DO_1") (pintype "bidirectional"))
      (node (ref "Led23") (pin "3") (pinfunction "DI_3") (pintype "bidirectional"))
    )
    (net (code "37") (name "Net-(Led23-DO)") (class "Default")
      (node (ref "Led23") (pin "1") (pinfunction "DO_1") (pintype "bidirectional"))
      (node (ref "Led24") (pin "3") (pinfunction "DI_3") (pintype "bidirectional"))
    )
    (net (code "38") (name "VCC") (class "Default")
      (node (ref "C4") (pin "2") (pinfunction "2_2") (pintype "passive"))
      (node (ref "IC") (pin "18") (pinfunction "AVCC_18") (pintype "power_in"))
      (node (ref "IC") (pin "4") (pinfunction "VCC_4") (pintype "power_in"))
      (node (ref "IC") (pin "6") (pinfunction "VCC_6") (pintype "power_in"))
      (node (ref "R1") (pin "1") (pinfunction "1_1") (pintype "passive"))
      (node (ref "SW2") (pin "2") (pinfunction "2_2") (pintype "passive"))
      (node (ref "U1") (pin "5") (pinfunction "VOUT_5") (pintype "output"))
    )
    (net (code "39") (name "unconnected-(IC-ADC6-Pad19)") (class "Default")
      (node (ref "IC") (pin "19") (pinfunction "ADC6_19") (pintype "bidirectional+no_connect"))
    )
    (net (code "40") (name "unconnected-(IC-ADC7-Pad22)") (class "Default")
      (node (ref "IC") (pin "22") (pinfunction "ADC7_22") (pintype "bidirectional+no_connect"))
    )
    (net (code "41") (name "unconnected-(IC-PB0-Pad12)") (class "Default")
      (node (ref "IC") (pin "12") (pinfunction "PB0_12") (pintype "bidirectional+no_connect"))
    )
    (net (code "42") (name "unconnected-(IC-PB1-Pad13)") (class "Default")
      (node (ref "IC") (pin "13") (pinfunction "PB1_13") (pintype "bidirectional+no_connect"))
    )
    (net (code "43") (name "unconnected-(IC-PB2-Pad14)") (class "Default")
      (node (ref "IC") (pin "14") (pinfunction "PB2_14") (pintype "bidirectional+no_connect"))
    )
    (net (code "44") (name "unconnected-(IC-PC0-Pad23)") (class "Default")
      (node (ref "IC") (pin "23") (pinfunction "PC0_23") (pintype "bidirectional+no_connect"))
    )
    (net (code "45") (name "unconnected-(IC-PC1-Pad24)") (class "Default")
      (node (ref "IC") (pin "24") (pinfunction "PC1_24") (pintype "bidirectional+no_connect"))
    )
    (net (code "46") (name "unconnected-(IC-PC2-Pad25)") (class "Default")
      (node (ref "IC") (pin "25") (pinfunction "PC2_25") (pintype "bidirectional+no_connect"))
    )
    (net (code "47") (name "unconnected-(IC-PC3-Pad26)") (class "Default")
      (node (ref "IC") (pin "26") (pinfunction "PC3_26") (pintype "bidirectional+no_connect"))
    )
    (net (code "48") (name "unconnected-(IC-PC4-Pad27)") (class "Default")
      (node (ref "IC") (pin "27") (pinfunction "PC4_27") (pintype "bidirectional+no_connect"))
    )
    (net (code "49") (name "unconnected-(IC-PC5-Pad28)") (class "Default")
      (node (ref "IC") (pin "28") (pinfunction "PC5_28") (pintype "bidirectional+no_connect"))
    )
    (net (code "50") (name "unconnected-(IC-PD3-Pad1)") (class "Default")
      (node (ref "IC") (pin "1") (pinfunction "PD3_1") (pintype "bidirectional+no_connect"))
    )
    (net (code "51") (name "unconnected-(IC-PD4-Pad2)") (class "Default")
      (node (ref "IC") (pin "2") (pinfunction "PD4_2") (pintype "bidirectional+no_connect"))
    )
    (net (code "52") (name "unconnected-(IC-PD7-Pad11)") (class "Default")
      (node (ref "IC") (pin "11") (pinfunction "PD7_11") (pintype "bidirectional+no_connect"))
    )
    (net (code "53") (name "unconnected-(Led24-DO-Pad1)") (class "Default")
      (node (ref "Led24") (pin "1") (pinfunction "DO_1") (pintype "bidirectional+no_connect"))
    )
  )
)
